# EPS_Distribution_Measurements.net
KiCad netlist of a schematic drawn in Altium Designer
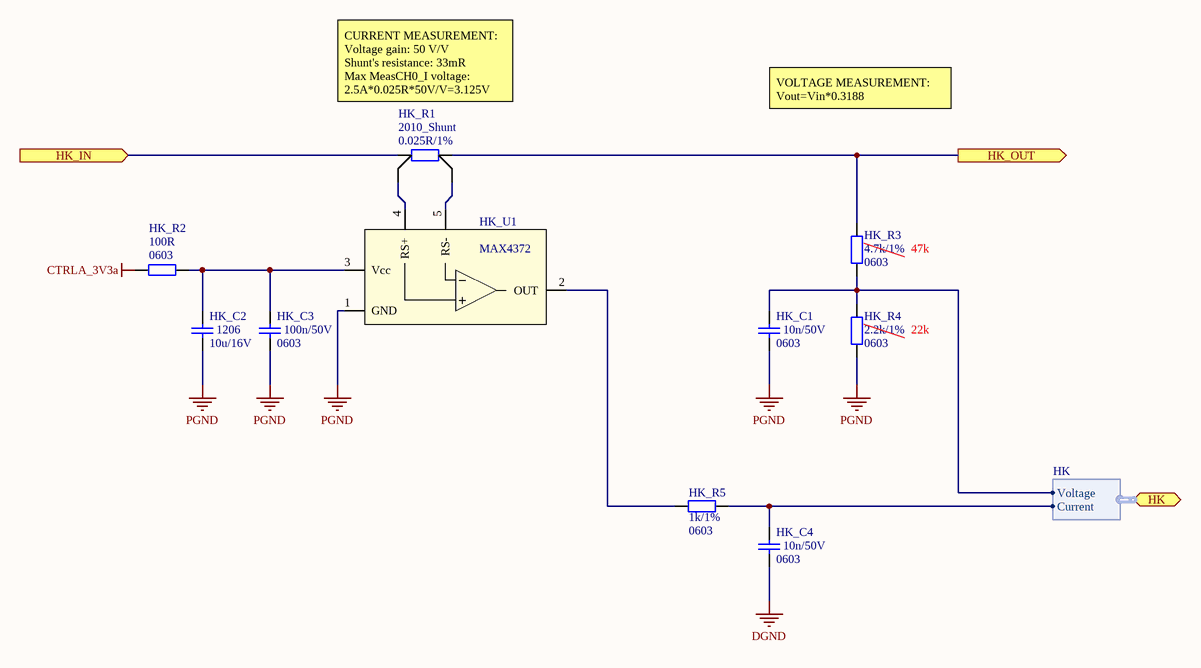
[diagram p0: EPS_Distribution_Measurements.SchDoc]

(export (version "E")
  (design (tool "Eeschema 10.0.6"))
  (components
    (comp (ref "HK_C1")
      (value "10n/50V")
      (footprint "SMD_Capacitor_0603")
      (description "Ceramic Cap Kemet COTS 100n/50V X7R 0603")
      (fields
        (field (name "MANUFACTURER") "Kemet")
        (field (name "MANUFACTURERPARTNUMBER") "C0603T104K5RALTU")
        (field (name "PACKAGE") "0603")
      )
      (libsource (lib "capacitors") (part "Cer_C0603T104K5RALTU"))
    )
    (comp (ref "HK_C2")
      (value "10u/16V")
      (footprint "SMD_Capacitor_1206")
      (description "Ceramic Cap Kemet COTS 10u/16V X7R 1206")
      (fields
        (field (name "MANUFACTURERPARTNUMBER") "C1206T106K4RACTU")
        (field (name "MANUFACTURER") "Kemet")
        (field (name "PACKGE") "1206")
      )
      (libsource (lib "capacitors") (part "Cer_C1206T106K4RACTU"))
    )
    (comp (ref "HK_C3")
      (value "100n/50V")
      (footprint "SMD_Capacitor_0603")
      (description "Ceramic Cap Kemet COTS 100n/50V X7R 0603")
      (fields
        (field (name "MANUFACTURER") "Kemet")
        (field (name "MANUFACTURERPARTNUMBER") "C0603T104K5RALTU")
        (field (name "PACKAGE") "0603")
      )
      (libsource (lib "capacitors") (part "Cer_C0603T104K5RALTU"))
    )
    (comp (ref "HK_C4")
      (value "10n/50V")
      (footprint "SMD_Capacitor_0603")
      (description "Ceramic Cap Kemet COTS 100n/50V X7R 0603")
      (fields
        (field (name "MANUFACTURER") "Kemet")
        (field (name "MANUFACTURERPARTNUMBER") "C0603T104K5RALTU")
        (field (name "PACKAGE") "0603")
      )
      (libsource (lib "capacitors") (part "Cer_C0603T104K5RALTU"))
    )
    (comp (ref "HK_R1")
      (value "0.025R/1%")
      (footprint "SMD_Resistor-shunt_2010")
      (description "1W current sensing shunt resistor")
      (fields
        (field (name "MANUFACTURER") "Viking")
        (field (name "MANUFACTURERPARTNUMBER") "CS10FTHTR025")
        (field (name "PACKAGE") "2010_Shunt")
      )
      (libsource (lib "resistors") (part "CS10FTHTR025"))
    )
    (comp (ref "HK_R2")
      (value "100R")
      (footprint "SMD_Resistor_0603")
      (fields (field (name "PACKAGE") "0603"))
      (libsource (lib "") (part "Res_1"))
    )
    (comp (ref "HK_R3")
      (value "4.7k/1%")
      (footprint "SMD_Resistor_0603")
      (fields (field (name "PACKAGE") "0603"))
      (libsource (lib "resistors") (part "Res"))
    )
    (comp (ref "HK_R4")
      (value "2.2k/1%")
      (footprint "SMD_Resistor_0603")
      (fields (field (name "PACKAGE") "0603"))
      (libsource (lib "resistors") (part "Res"))
    )
    (comp (ref "HK_R5")
      (value "1k/1%")
      (footprint "SMD_Resistor_0603")
      (fields (field (name "PACKAGE") "0603"))
      (libsource (lib "") (part "Res_1"))
    )
    (comp (ref "HK_U1")
      (value "MAX4372")
      (footprint "SOT23-5")
      (description "High-Side Current-Sense Amplifier with Voltage Output")
      (fields (field (name "MANUFACTURER") "Maxim Integrated Products"))
      (libsource (lib "microcircuits") (part "MAX4372"))
    )
  )
  (nets
    (net (code "2") (name "/HK_IN") (class "Default")
      (node (ref "HK_R1") (pin "4") (pinfunction "4_4") (pintype "passive"))
    )
    (net (code "3") (name "/HK_OUT") (class "Default")
      (node (ref "HK_R1") (pin "1") (pinfunction "1_1") (pintype "passive"))
      (node (ref "HK_R3") (pin "1") (pinfunction "1_1") (pintype "passive"))
    )
    (net (code "5") (name "CTRLA_3V3a") (class "Default")
      (node (ref "HK_R2") (pin "1") (pinfunction "1_1") (pintype "passive"))
    )
    (net (code "6") (name "DGND") (class "Default")
      (node (ref "HK_C4") (pin "2") (pinfunction "2_2") (pintype "passive"))
    )
    (net (code "7") (name "Net-(HK_C1-Pad1)") (class "Default")
      (node (ref "HK_C1") (pin "1") (pinfunction "1_1") (pintype "passive"))
      (node (ref "HK_R3") (pin "2") (pinfunction "2_2") (pintype "passive"))
      (node (ref "HK_R4") (pin "1") (pinfunction "1_1") (pintype "passive"))
    )
    (net (code "8") (name "Net-(HK_C4-Pad1)") (class "Default")
      (node (ref "HK_C4") (pin "1") (pinfunction "1_1") (pintype "passive"))
      (node (ref "HK_R5") (pin "2") (pinfunction "2_2") (pintype "passive"))
    )
    (net (code "9") (name "Net-(HK_U1-OUT)") (class "Default")
      (node (ref "HK_R5") (pin "1") (pinfunction "1_1") (pintype "passive"))
      (node (ref "HK_U1") (pin "2") (pinfunction "OUT_2") (pintype "passive"))
    )
    (net (code "10") (name "Net-(HK_U1-RS+)") (class "Default")
      (node (ref "HK_R1") (pin "3") (pinfunction "3_3") (pintype "passive"))
      (node (ref "HK_U1") (pin "4") (pinfunction "RS+_4") (pintype "passive"))
    )
    (net (code "11") (name "Net-(HK_U1-RS-)") (class "Default")
      (node (ref "HK_R1") (pin "2") (pinfunction "2_2") (pintype "passive"))
      (node (ref "HK_U1") (pin "5") (pinfunction "RS-_5") (pintype "passive"))
    )
    (net (code "12") (name "Net-(HK_U1-Vcc)") (class "Default")
      (node (ref "HK_C2") (pin "1") (pinfunction "1_1") (pintype "passive"))
      (node (ref "HK_C3") (pin "1") (pinfunction "1_1") (pintype "passive"))
      (node (ref "HK_R2") (pin "2") (pinfunction "2_2") (pintype "passive"))
      (node (ref "HK_U1") (pin "3") (pinfunction "Vcc_3") (pintype "passive"))
    )
    (net (code "13") (name "PGND") (class "Default")
      (node (ref "HK_C1") (pin "2") (pinfunction "2_2") (pintype "passive"))
      (node (ref "HK_C2") (pin "2") (pinfunction "2_2") (pintype "passive"))
      (node (ref "HK_C3") (pin "2") (pinfunction "2_2") (pintype "passive"))
      (node (ref "HK_R4") (pin "2") (pinfunction "2_2") (pintype "passive"))
      (node (ref "HK_U1") (pin "1") (pinfunction "GND_1") (pintype "passive"))
    )
  )
)
